# LCmeter0-LCD3310-8pinlcd-PIC-COMP.net
KiCad netlist of a schematic drawn in EAGLE
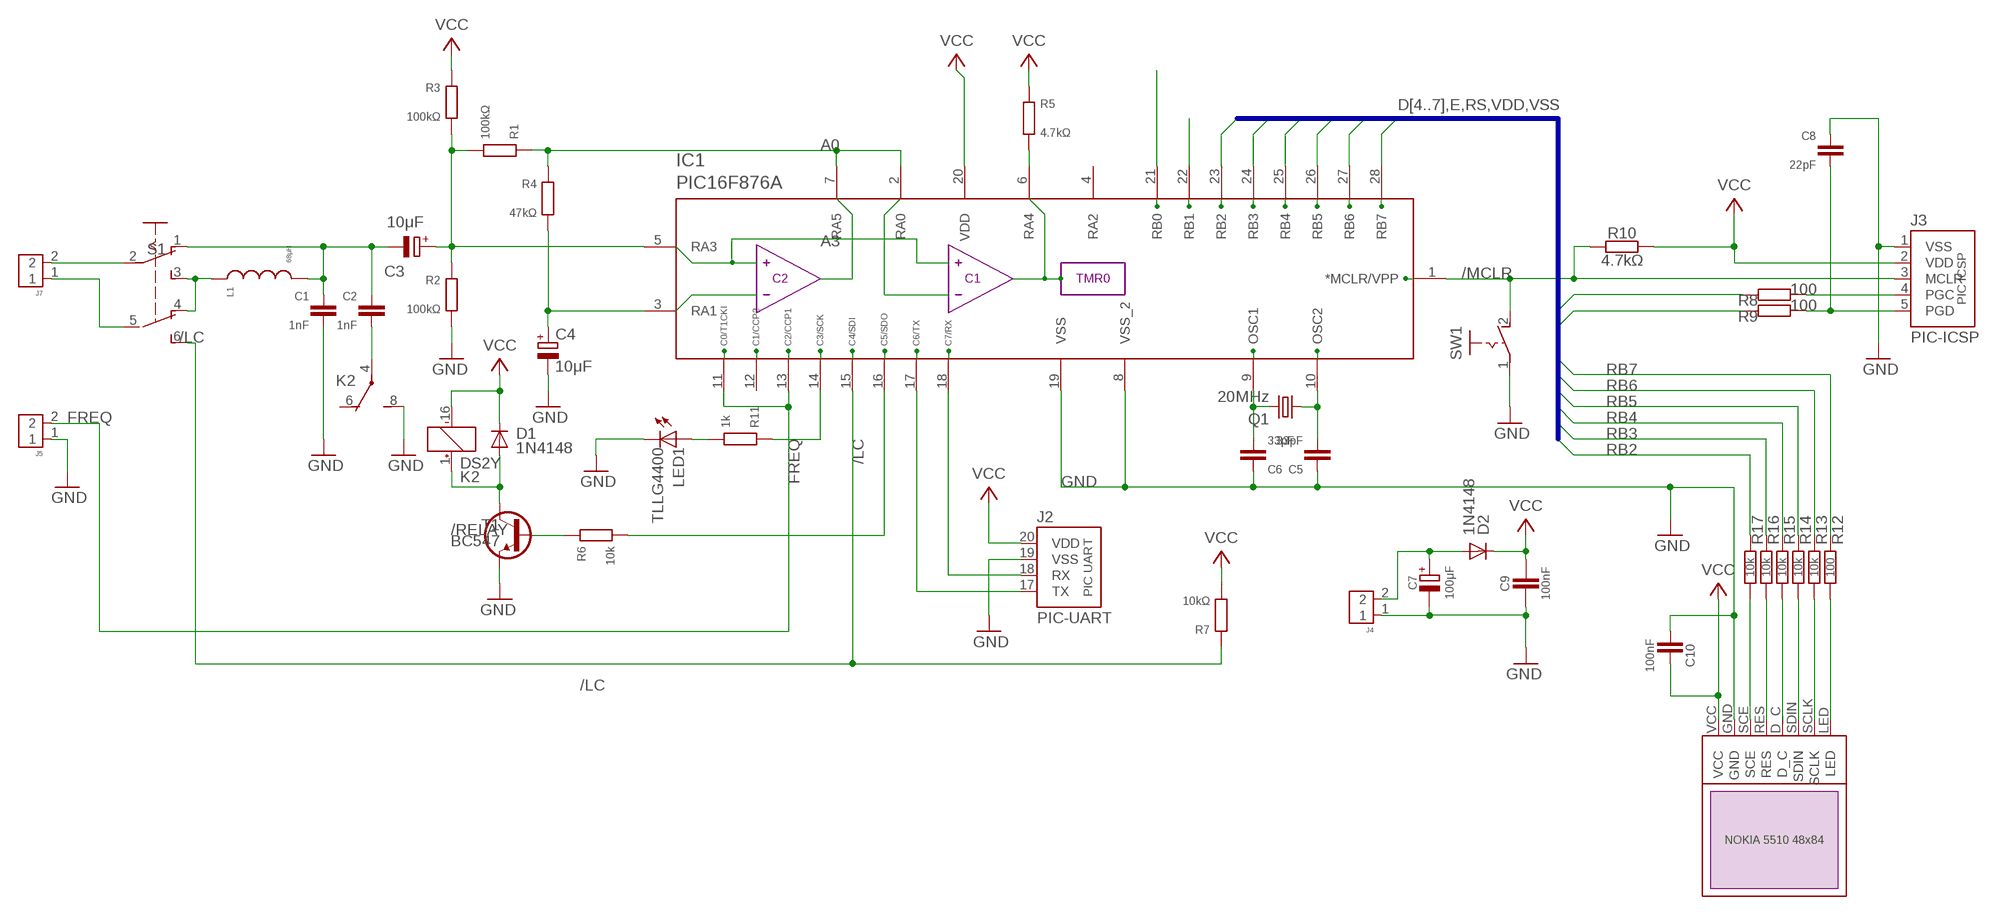
[diagram p0: schematic, sheet 1]

(export (version "E")
  (design (tool "Eeschema 10.0.6"))
  (components
    (comp (ref "C1")
      (value "1nF")
      (footprint "eagle-import:C050-025X060")
      (libsource (lib "eagle-import") (part "C025-025X060"))
    )
    (comp (ref "C2")
      (value "1nF")
      (footprint "eagle-import:C050-025X060")
      (libsource (lib "eagle-import") (part "C025-025X060"))
    )
    (comp (ref "C3")
      (value "10μF")
      (footprint "eagle-import:E2,5-4")
      (libsource (lib "eagle-import") (part "CPOLE2,5-4"))
    )
    (comp (ref "C4")
      (value "10μF")
      (footprint "eagle-import:E2,5-4")
      (libsource (lib "eagle-import") (part "CPOLE2,5-4"))
    )
    (comp (ref "C5")
      (value "33pF")
      (footprint "eagle-import:C025-020X036")
      (libsource (lib "eagle-import") (part "C025-020X036"))
    )
    (comp (ref "C6")
      (value "33pF")
      (footprint "eagle-import:C025-020X036")
      (libsource (lib "eagle-import") (part "C025-020X036"))
    )
    (comp (ref "C7")
      (value "100μF")
      (footprint "eagle-import:E5-5")
      (libsource (lib "eagle-import") (part "CPOLE5-5"))
    )
    (comp (ref "C8")
      (value "22pF")
      (footprint "eagle-import:C050-020X036")
      (libsource (lib "eagle-import") (part "C050-020X036"))
    )
    (comp (ref "C9")
      (value "100nF")
      (footprint "eagle-import:C025-024X044")
      (libsource (lib "eagle-import") (part "C-EU025-024X044"))
    )
    (comp (ref "C10")
      (value "100nF")
      (footprint "eagle-import:C025-015X024_V")
      (libsource (lib "eagle-import") (part "C025-015X024"))
    )
    (comp (ref "D1")
      (value "1N4148")
      (footprint "eagle-import:DO34-7")
      (libsource (lib "eagle-import") (part "1N414834-7"))
    )
    (comp (ref "D2")
      (value "1N4148")
      (footprint "eagle-import:DO34-10V")
      (libsource (lib "eagle-import") (part "1N414834-10V"))
    )
    (comp (ref "IC1")
      (value "PIC16F876A")
      (footprint "eagle-import:DIL28-3_V")
      (libsource (lib "eagle-import") (part "PIC16F876A-X/SP-COMPDIL28-3/V"))
    )
    (comp (ref "J2")
      (value "PIC-UART")
      (footprint "eagle-import:PIC-UART")
      (libsource (lib "eagle-import") (part "PIC-UART"))
    )
    (comp (ref "J3")
      (value "PIC-ICSP")
      (footprint "eagle-import:PIC-ICSP")
      (libsource (lib "eagle-import") (part "PIC-ICSPICSP"))
    )
    (comp (ref "J4")
      (value "J4")
      (footprint "eagle-import:CONN-2P")
      (libsource (lib "eagle-import") (part "CONN-2P2P/H"))
    )
    (comp (ref "J5")
      (value "CONN-2P2P/V")
      (footprint "eagle-import:CONN-2P-V")
      (libsource (lib "eagle-import") (part "CONN-2P2P/V"))
    )
    (comp (ref "J6")
      (value "NOKIA-5510-48X84")
      (footprint "eagle-import:CONN-LCD5510")
      (libsource (lib "eagle-import") (part "NOKIA-5510-48X84"))
    )
    (comp (ref "J7")
      (value "CONN-2P2P/V")
      (footprint "eagle-import:CONN-2P-V")
      (libsource (lib "eagle-import") (part "CONN-2P2P/V"))
    )
    (comp (ref "K2")
      (value "DS2Y")
      (footprint "eagle-import:DS2Y")
      (fields (field (name "MPN") "DS2Y-S-DC5V"))
      (libsource (lib "eagle-import") (part "DS2Y-S-DC5V"))
    )
    (comp (ref "L1")
      (value "68μH")
      (footprint "eagle-import:L-8R")
      (libsource (lib "eagle-import") (part "L-09R"))
    )
    (comp (ref "LED1")
      (value "TLLG4400")
      (footprint "eagle-import:LED3MM")
      (fields (field (name "MF") "VISHAY SEMICONDUCTOR"))
      (libsource (lib "eagle-import") (part "TLLG4400"))
    )
    (comp (ref "Q1")
      (value "20MHz")
      (footprint "eagle-import:HC49")
      (libsource (lib "eagle-import") (part "CRYSTALHC49"))
    )
    (comp (ref "R1")
      (value "100kΩ")
      (footprint "eagle-import:0202_7")
      (libsource (lib "eagle-import") (part "R0202/7"))
    )
    (comp (ref "R2")
      (value "100kΩ")
      (footprint "eagle-import:0202_7")
      (libsource (lib "eagle-import") (part "R0202/7"))
    )
    (comp (ref "R3")
      (value "100kΩ")
      (footprint "eagle-import:0202_7")
      (libsource (lib "eagle-import") (part "R0202/7"))
    )
    (comp (ref "R4")
      (value "47kΩ")
      (footprint "eagle-import:0202_7")
      (libsource (lib "eagle-import") (part "R0202/7"))
    )
    (comp (ref "R5")
      (value "4.7kΩ")
      (footprint "eagle-import:0202_7")
      (libsource (lib "eagle-import") (part "R0202/7"))
    )
    (comp (ref "R6")
      (value "10k")
      (footprint "eagle-import:0202_7-V")
      (libsource (lib "eagle-import") (part "R0202/7-V"))
    )
    (comp (ref "R7")
      (value "10kΩ")
      (footprint "eagle-import:0202_10-V")
      (libsource (lib "eagle-import") (part "R0202/10-V"))
    )
    (comp (ref "R8")
      (value "100")
      (footprint "eagle-import:0202_7")
      (libsource (lib "eagle-import") (part "R0202/7"))
    )
    (comp (ref "R9")
      (value "100")
      (footprint "eagle-import:0202_2V")
      (libsource (lib "eagle-import") (part "R0202/2V"))
    )
    (comp (ref "R10")
      (value "4.7kΩ")
      (footprint "eagle-import:0202_7")
      (libsource (lib "eagle-import") (part "R0202/7"))
    )
    (comp (ref "R11")
      (value "1k")
      (footprint "eagle-import:0202_5-V")
      (libsource (lib "eagle-import") (part "R0202/5-V"))
    )
    (comp (ref "R12")
      (value "100")
      (footprint "eagle-import:0202_7")
      (libsource (lib "eagle-import") (part "R0202/7"))
    )
    (comp (ref "R13")
      (value "10k")
      (footprint "eagle-import:0202_7")
      (libsource (lib "eagle-import") (part "R0202/7"))
    )
    (comp (ref "R14")
      (value "10k")
      (footprint "eagle-import:0202_7")
      (libsource (lib "eagle-import") (part "R0202/7"))
    )
    (comp (ref "R15")
      (value "10k")
      (footprint "eagle-import:0202_7")
      (libsource (lib "eagle-import") (part "R0202/7"))
    )
    (comp (ref "R16")
      (value "10k")
      (footprint "eagle-import:0202_7")
      (libsource (lib "eagle-import") (part "R0202/7"))
    )
    (comp (ref "R17")
      (value "10k")
      (footprint "eagle-import:0202_7")
      (libsource (lib "eagle-import") (part "R0202/7"))
    )
    (comp (ref "S1")
      (value "SL-SW-2P-2T-H")
      (footprint "eagle-import:SLSW-2P2T-H")
      (libsource (lib "eagle-import") (part "SL-SW-2P-2T-H"))
    )
    (comp (ref "SW1")
      (value "PB-1P-1T")
      (footprint "eagle-import:PB-1P1T")
      (libsource (lib "eagle-import") (part "PB-1P-1T"))
    )
    (comp (ref "T1")
      (value "BC547")
      (footprint "eagle-import:TO92-CBE-A")
      (libsource (lib "eagle-import") (part "BC547CBE-A"))
    )
  )
  (nets
    (net (code "5") (name "/A0") (class "Default")
      (node (ref "IC1") (pin "2") (pinfunction "RA0_2") (pintype "passive"))
      (node (ref "IC1") (pin "7") (pinfunction "RA5_7") (pintype "passive"))
      (node (ref "R1") (pin "2") (pinfunction "2_2") (pintype "passive"))
      (node (ref "R4") (pin "2") (pinfunction "2_2") (pintype "passive"))
    )
    (net (code "6") (name "/A3") (class "Default")
      (node (ref "C3") (pin "+") (pinfunction "+_+") (pintype "passive"))
      (node (ref "IC1") (pin "5") (pinfunction "RA3_5") (pintype "passive"))
      (node (ref "R1") (pin "1") (pinfunction "1_1") (pintype "passive"))
      (node (ref "R2") (pin "2") (pinfunction "2_2") (pintype "passive"))
      (node (ref "R3") (pin "1") (pinfunction "1_1") (pintype "passive"))
    )
    (net (code "7") (name "/FREQ") (class "Default")
      (node (ref "IC1") (pin "11") (pinfunction "RC0_11") (pintype "passive"))
      (node (ref "IC1") (pin "13") (pinfunction "RC2_13") (pintype "passive"))
      (node (ref "J5") (pin "2") (pinfunction "2_2") (pintype "bidirectional"))
    )
    (net (code "8") (name "/RB2") (class "Default")
      (node (ref "IC1") (pin "23") (pinfunction "RB2_23") (pintype "passive"))
      (node (ref "R17") (pin "2") (pinfunction "2_2") (pintype "passive"))
    )
    (net (code "9") (name "/RB3") (class "Default")
      (node (ref "IC1") (pin "24") (pinfunction "RB3_24") (pintype "passive"))
      (node (ref "R16") (pin "2") (pinfunction "2_2") (pintype "passive"))
    )
    (net (code "10") (name "/RB4") (class "Default")
      (node (ref "IC1") (pin "25") (pinfunction "RB4_25") (pintype "passive"))
      (node (ref "R15") (pin "2") (pinfunction "2_2") (pintype "passive"))
    )
    (net (code "11") (name "/RB5") (class "Default")
      (node (ref "IC1") (pin "26") (pinfunction "RB5_26") (pintype "passive"))
      (node (ref "R14") (pin "2") (pinfunction "2_2") (pintype "passive"))
    )
    (net (code "12") (name "/RB6") (class "Default")
      (node (ref "IC1") (pin "27") (pinfunction "RB6_27") (pintype "passive"))
      (node (ref "R13") (pin "2") (pinfunction "2_2") (pintype "passive"))
      (node (ref "R8") (pin "2") (pinfunction "2_2") (pintype "passive"))
    )
    (net (code "13") (name "/RB7") (class "Default")
      (node (ref "IC1") (pin "28") (pinfunction "RB7_28") (pintype "passive"))
      (node (ref "R12") (pin "2") (pinfunction "2_2") (pintype "passive"))
      (node (ref "R9") (pin "2") (pinfunction "2_2") (pintype "passive"))
    )
    (net (code "15") (name "/{slash}LC") (class "Default")
      (node (ref "IC1") (pin "15") (pinfunction "RC4_15") (pintype "passive"))
      (node (ref "R7") (pin "2") (pinfunction "2_2") (pintype "passive"))
      (node (ref "S1") (pin "6") (pinfunction "S1_6") (pintype "passive"))
    )
    (net (code "16") (name "/{slash}MCLR") (class "Default")
      (node (ref "IC1") (pin "1") (pinfunction "*MCLR/VPP_1") (pintype "passive"))
      (node (ref "J3") (pin "3") (pinfunction "MCLR_3") (pintype "passive"))
      (node (ref "R10") (pin "2") (pinfunction "2_2") (pintype "passive"))
      (node (ref "SW1") (pin "2") (pinfunction "S_2") (pintype "passive"))
    )
    (net (code "17") (name "/{slash}RELAY") (class "Default")
      (node (ref "D1") (pin "A") (pinfunction "A_A") (pintype "passive"))
      (node (ref "K2") (pin "1") (pinfunction "+_1") (pintype "passive"))
      (node (ref "T1") (pin "C") (pinfunction "C_C") (pintype "passive"))
    )
    (net (code "18") (name "GND") (class "Default")
      (node (ref "C1") (pin "2") (pinfunction "2_2") (pintype "passive"))
      (node (ref "C10") (pin "1") (pinfunction "1_1") (pintype "passive"))
      (node (ref "C4") (pin "-") (pinfunction "-_-") (pintype "passive"))
      (node (ref "C5") (pin "1") (pinfunction "1_1") (pintype "passive"))
      (node (ref "C6") (pin "1") (pinfunction "1_1") (pintype "passive"))
      (node (ref "C7") (pin "-") (pinfunction "-_-") (pintype "passive"))
      (node (ref "C8") (pin "1") (pinfunction "1_1") (pintype "passive"))
      (node (ref "C9") (pin "2") (pinfunction "2_2") (pintype "passive"))
      (node (ref "IC1") (pin "19") (pinfunction "VSS_19") (pintype "passive"))
      (node (ref "IC1") (pin "8") (pinfunction "VSS_2_8") (pintype "passive"))
      (node (ref "J2") (pin "19") (pinfunction "VSS_19") (pintype "passive"))
      (node (ref "J3") (pin "1") (pinfunction "VSS_1") (pintype "passive"))
      (node (ref "J4") (pin "1") (pinfunction "1_1") (pintype "bidirectional"))
      (node (ref "J5") (pin "1") (pinfunction "1_1") (pintype "bidirectional"))
      (node (ref "J6") (pin "GND") (pinfunction "GND_GND") (pintype "passive"))
      (node (ref "K2") (pin "8") (pinfunction "S_8") (pintype "passive"))
      (node (ref "LED1") (pin "K") (pinfunction "C_K") (pintype "passive"))
      (node (ref "R2") (pin "1") (pinfunction "1_1") (pintype "passive"))
      (node (ref "SW1") (pin "1") (pinfunction "P_1") (pintype "passive"))
      (node (ref "T1") (pin "E") (pinfunction "E_E") (pintype "passive"))
    )
    (net (code "19") (name "Net-(C7-Pad+)") (class "Default")
      (node (ref "C7") (pin "+") (pinfunction "+_+") (pintype "passive"))
      (node (ref "D2") (pin "A") (pinfunction "A_A") (pintype "passive"))
      (node (ref "J4") (pin "2") (pinfunction "2_2") (pintype "bidirectional"))
    )
    (net (code "20") (name "Net-(IC1-OSC1)") (class "Default")
      (node (ref "C6") (pin "2") (pinfunction "2_2") (pintype "passive"))
      (node (ref "IC1") (pin "9") (pinfunction "OSC1_9") (pintype "passive"))
      (node (ref "Q1") (pin "2") (pinfunction "2_2") (pintype "passive"))
    )
    (net (code "21") (name "Net-(IC1-OSC2)") (class "Default")
      (node (ref "C5") (pin "2") (pinfunction "2_2") (pintype "passive"))
      (node (ref "IC1") (pin "10") (pinfunction "OSC2_10") (pintype "passive"))
      (node (ref "Q1") (pin "1") (pinfunction "1_1") (pintype "passive"))
    )
    (net (code "22") (name "Net-(IC1-RA1)") (class "Default")
      (node (ref "C4") (pin "+") (pinfunction "+_+") (pintype "passive"))
      (node (ref "IC1") (pin "3") (pinfunction "RA1_3") (pintype "passive"))
      (node (ref "R4") (pin "1") (pinfunction "1_1") (pintype "passive"))
    )
    (net (code "23") (name "Net-(IC1-RA4)") (class "Default")
      (node (ref "IC1") (pin "6") (pinfunction "RA4_6") (pintype "passive"))
      (node (ref "R5") (pin "1") (pinfunction "1_1") (pintype "passive"))
    )
    (net (code "24") (name "Net-(IC1-RC3)") (class "Default")
      (node (ref "IC1") (pin "14") (pinfunction "RC3_14") (pintype "passive"))
      (node (ref "R11") (pin "2") (pinfunction "2_2") (pintype "passive"))
    )
    (net (code "25") (name "Net-(IC1-RC5)") (class "Default")
      (node (ref "IC1") (pin "16") (pinfunction "RC5_16") (pintype "passive"))
      (node (ref "R6") (pin "1") (pinfunction "1_1") (pintype "passive"))
    )
    (net (code "26") (name "Net-(IC1-RC6)") (class "Default")
      (node (ref "IC1") (pin "17") (pinfunction "RC6_17") (pintype "passive"))
      (node (ref "J2") (pin "17") (pinfunction "TX_17") (pintype "passive"))
    )
    (net (code "27") (name "Net-(IC1-RC7)") (class "Default")
      (node (ref "IC1") (pin "18") (pinfunction "RC7_18") (pintype "passive"))
      (node (ref "J2") (pin "18") (pinfunction "RX_18") (pintype "passive"))
    )
    (net (code "28") (name "Net-(J3-PGC)") (class "Default")
      (node (ref "J3") (pin "4") (pinfunction "PGC_4") (pintype "passive"))
      (node (ref "R8") (pin "1") (pinfunction "1_1") (pintype "passive"))
    )
    (net (code "29") (name "Net-(J3-PGD)") (class "Default")
      (node (ref "C8") (pin "2") (pinfunction "2_2") (pintype "passive"))
      (node (ref "J3") (pin "5") (pinfunction "PGD_5") (pintype "passive"))
      (node (ref "R9") (pin "1") (pinfunction "1_1") (pintype "passive"))
    )
    (net (code "30") (name "Net-(J6-PadD_C)") (class "Default")
      (node (ref "J6") (pin "D_C") (pinfunction "D_C_D_C") (pintype "passive"))
      (node (ref "R15") (pin "1") (pinfunction "1_1") (pintype "passive"))
    )
    (net (code "31") (name "Net-(J6-PadLED)") (class "Default")
      (node (ref "J6") (pin "LED") (pinfunction "LED_LED") (pintype "passive"))
      (node (ref "R12") (pin "1") (pinfunction "1_1") (pintype "passive"))
    )
    (net (code "32") (name "Net-(J6-PadRES)") (class "Default")
      (node (ref "J6") (pin "RES") (pinfunction "RES_RES") (pintype "passive"))
      (node (ref "R16") (pin "1") (pinfunction "1_1") (pintype "passive"))
    )
    (net (code "33") (name "Net-(J6-PadSCE)") (class "Default")
      (node (ref "J6") (pin "SCE") (pinfunction "SCE_SCE") (pintype "passive"))
      (node (ref "R17") (pin "1") (pinfunction "1_1") (pintype "passive"))
    )
    (net (code "34") (name "Net-(J6-PadSCLK)") (class "Default")
      (node (ref "J6") (pin "SCLK") (pinfunction "SCLK_SCLK") (pintype "passive"))
      (node (ref "R13") (pin "1") (pinfunction "1_1") (pintype "passive"))
    )
    (net (code "35") (name "Net-(J6-PadSDIN)") (class "Default")
      (node (ref "J6") (pin "SDIN") (pinfunction "SDIN_SDIN") (pintype "passive"))
      (node (ref "R14") (pin "1") (pinfunction "1_1") (pintype "passive"))
    )
    (net (code "36") (name "Net-(K2B-P)") (class "Default")
      (node (ref "C2") (pin "2") (pinfunction "2_2") (pintype "passive"))
      (node (ref "K2") (pin "4") (pinfunction "P_4") (pintype "passive"))
    )
    (net (code "37") (name "Net-(L1-1)") (class "Default")
      (node (ref "L1") (pin "P$1") (pinfunction "1_P$1") (pintype "passive"))
      (node (ref "S1") (pin "3") (pinfunction "S_3") (pintype "passive"))
      (node (ref "S1") (pin "4") (pinfunction "O1_4") (pintype "passive"))
    )
    (net (code "38") (name "Net-(L1-2)") (class "Default")
      (node (ref "C1") (pin "1") (pinfunction "1_1") (pintype "passive"))
      (node (ref "C2") (pin "1") (pinfunction "1_1") (pintype "passive"))
      (node (ref "C3") (pin "-") (pinfunction "-_-") (pintype "passive"))
      (node (ref "L1") (pin "P$2") (pinfunction "2_P$2") (pintype "passive"))
      (node (ref "S1") (pin "1") (pinfunction "O_1") (pintype "passive"))
    )
    (net (code "39") (name "Net-(LED1-PadA)") (class "Default")
      (node (ref "LED1") (pin "A") (pinfunction "A_A") (pintype "passive"))
      (node (ref "R11") (pin "1") (pinfunction "1_1") (pintype "passive"))
    )
    (net (code "40") (name "Net-(R6-Pad2)") (class "Default")
      (node (ref "R6") (pin "2") (pinfunction "2_2") (pintype "passive"))
      (node (ref "T1") (pin "B") (pinfunction "B_B") (pintype "passive"))
    )
    (net (code "41") (name "Net-(S1-P)") (class "Default")
      (node (ref "J7") (pin "2") (pinfunction "2_2") (pintype "bidirectional"))
      (node (ref "S1") (pin "2") (pinfunction "P_2") (pintype "passive"))
    )
    (net (code "42") (name "Net-(S1-P1)") (class "Default")
      (node (ref "J7") (pin "1") (pinfunction "1_1") (pintype "bidirectional"))
      (node (ref "S1") (pin "5") (pinfunction "P1_5") (pintype "passive"))
    )
    (net (code "43") (name "VCC") (class "Default")
      (node (ref "C10") (pin "2") (pinfunction "2_2") (pintype "passive"))
      (node (ref "C9") (pin "1") (pinfunction "1_1") (pintype "passive"))
      (node (ref "D1") (pin "C") (pinfunction "C_C") (pintype "passive"))
      (node (ref "D2") (pin "C") (pinfunction "C_C") (pintype "passive"))
      (node (ref "IC1") (pin "20") (pinfunction "VDD_20") (pintype "passive"))
      (node (ref "J2") (pin "20") (pinfunction "VDD_20") (pintype "passive"))
      (node (ref "J3") (pin "2") (pinfunction "VDD_2") (pintype "passive"))
      (node (ref "J6") (pin "VCC") (pinfunction "VCC_VCC") (pintype "passive"))
      (node (ref "K2") (pin "16") (pinfunction "-_16") (pintype "passive"))
      (node (ref "R10") (pin "1") (pinfunction "1_1") (pintype "passive"))
      (node (ref "R3") (pin "2") (pinfunction "2_2") (pintype "passive"))
      (node (ref "R5") (pin "2") (pinfunction "2_2") (pintype "passive"))
      (node (ref "R7") (pin "1") (pinfunction "1_1") (pintype "passive"))
    )
    (net (code "44") (name "unconnected-(IC1-RA2-Pad4)") (class "Default")
      (node (ref "IC1") (pin "4") (pinfunction "RA2_4") (pintype "passive"))
    )
    (net (code "45") (name "unconnected-(IC1-RB0-Pad21)") (class "Default")
      (node (ref "IC1") (pin "21") (pinfunction "RB0_21") (pintype "passive"))
    )
    (net (code "46") (name "unconnected-(IC1-RB1-Pad22)") (class "Default")
      (node (ref "IC1") (pin "22") (pinfunction "RB1_22") (pintype "passive"))
    )
    (net (code "47") (name "unconnected-(IC1-RC1-Pad12)") (class "Default")
      (node (ref "IC1") (pin "12") (pinfunction "RC1_12") (pintype "passive"))
    )
    (net (code "48") (name "unconnected-(K2B-O-Pad6)") (class "Default")
      (node (ref "K2") (pin "6") (pinfunction "O_6") (pintype "passive"))
    )
  )
)
